# budzik.net
KiCad netlist of a schematic drawn in EAGLE
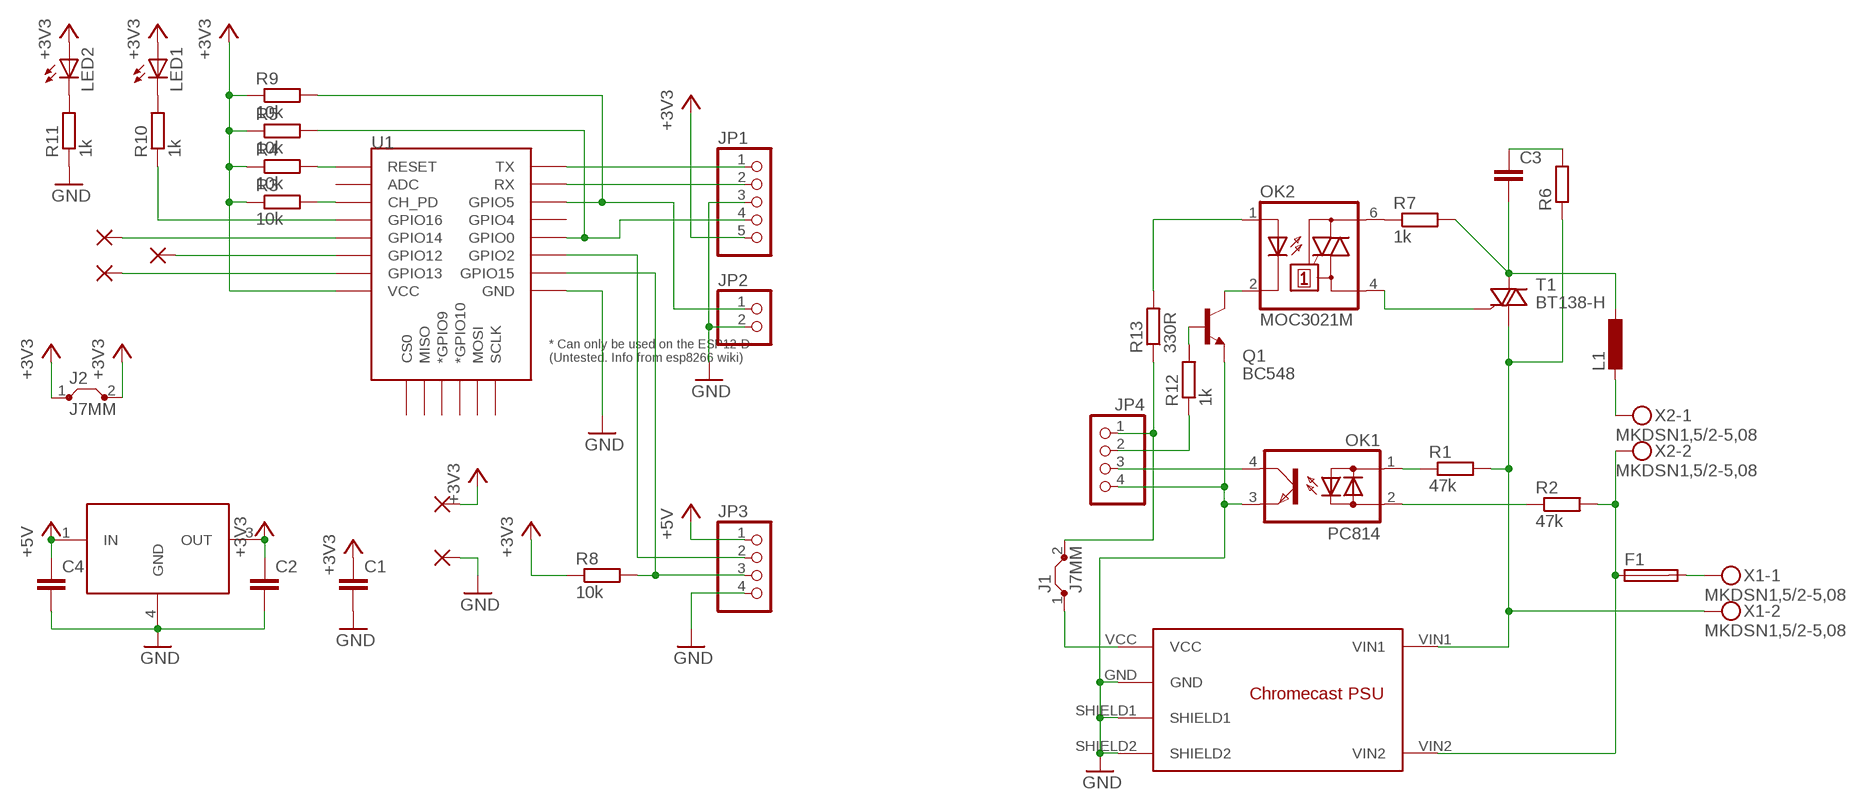
[diagram p0: schematic, sheet 1]

(export (version "E")
  (design (tool "Eeschema 10.0.6"))
  (components
    (comp (ref "C1")
      (value "C-EUC1206")
      (footprint "eagle-import:C1206")
      (libsource (lib "eagle-import") (part "C-EUC1206"))
    )
    (comp (ref "C2")
      (value "C-EUC1206K")
      (footprint "eagle-import:C1206K")
      (libsource (lib "eagle-import") (part "C-EUC1206K"))
    )
    (comp (ref "C3")
      (value "C-EU075-063X106")
      (footprint "eagle-import:C075-063X106")
      (libsource (lib "eagle-import") (part "resistor_C-EU075-063X106"))
    )
    (comp (ref "C4")
      (value "C-EUC1206K")
      (footprint "eagle-import:C1206K")
      (libsource (lib "eagle-import") (part "C-EUC1206K"))
    )
    (comp (ref "F1")
      (value "TR5")
      (footprint "eagle-import:TR5")
      (libsource (lib "eagle-import") (part "TR5"))
    )
    (comp (ref "J1")
      (value "J7MM")
      (footprint "eagle-import:07")
      (libsource (lib "eagle-import") (part "J7MM"))
    )
    (comp (ref "J2")
      (value "J7MM")
      (footprint "eagle-import:07")
      (libsource (lib "eagle-import") (part "J7MM"))
    )
    (comp (ref "JP1")
      (value "PINHD-1X5")
      (footprint "eagle-import:1X05")
      (libsource (lib "eagle-import") (part "PINHD-1X5"))
    )
    (comp (ref "JP2")
      (value "PINHD-1X2")
      (footprint "eagle-import:1X02")
      (libsource (lib "eagle-import") (part "PINHD-1X2"))
    )
    (comp (ref "JP3")
      (value "PINHD-1X4")
      (footprint "eagle-import:1X04")
      (libsource (lib "eagle-import") (part "PINHD-1X4"))
    )
    (comp (ref "JP4")
      (value "PINHD-1X4")
      (footprint "eagle-import:1X04")
      (libsource (lib "eagle-import") (part "PINHD-1X4"))
    )
    (comp (ref "L1")
      (value "L-EU6000-XXX-RC")
      (footprint "eagle-import:6000-XXXX-RC")
      (libsource (lib "eagle-import") (part "L-EU6000-XXX-RC"))
    )
    (comp (ref "LED1")
      (value "LEDSML0805")
      (footprint "eagle-import:SML0805")
      (libsource (lib "eagle-import") (part "LEDSML0805"))
    )
    (comp (ref "LED2")
      (value "LEDSML0805")
      (footprint "eagle-import:SML0805")
      (libsource (lib "eagle-import") (part "LEDSML0805"))
    )
    (comp (ref "OK1")
      (value "PC814")
      (footprint "eagle-import:DIL04")
      (libsource (lib "eagle-import") (part "PC814"))
    )
    (comp (ref "OK2")
      (value "MOC3021M")
      (footprint "eagle-import:DIL06")
      (fields (field (name "MF") "FAIRCHILD SEMICONDUCTOR") (field (name "MPN") "MOC3021-M"))
      (libsource (lib "eagle-import") (part "MOC30M21"))
    )
    (comp (ref "PAD1")
      (value "WIREPAD2,15/1,0")
      (footprint "eagle-import:2,15_1,0")
      (libsource (lib "eagle-import") (part "WIREPAD2,15/1,0"))
    )
    (comp (ref "PAD2")
      (value "WIREPAD2,15/1,0")
      (footprint "eagle-import:2,15_1,0")
      (libsource (lib "eagle-import") (part "WIREPAD2,15/1,0"))
    )
    (comp (ref "PAD3")
      (value "WIREPAD2,15/1,0")
      (footprint "eagle-import:2,15_1,0")
      (libsource (lib "eagle-import") (part "WIREPAD2,15/1,0"))
    )
    (comp (ref "PAD4")
      (value "WIREPAD2,15/1,0")
      (footprint "eagle-import:2,15_1,0")
      (libsource (lib "eagle-import") (part "WIREPAD2,15/1,0"))
    )
    (comp (ref "PAD5")
      (value "WIREPAD2,15/1,0")
      (footprint "eagle-import:2,15_1,0")
      (libsource (lib "eagle-import") (part "WIREPAD2,15/1,0"))
    )
    (comp (ref "Q1")
      (value "BC548")
      (footprint "eagle-import:TO92-EBC")
      (libsource (lib "eagle-import") (part "BC548"))
    )
    (comp (ref "R1")
      (value "47k")
      (footprint "eagle-import:0204_7")
      (libsource (lib "eagle-import") (part "R-EU_0204/7"))
    )
    (comp (ref "R2")
      (value "47k")
      (footprint "eagle-import:0204_7")
      (libsource (lib "eagle-import") (part "R-EU_0204/7"))
    )
    (comp (ref "R3")
      (value "10k")
      (footprint "eagle-import:R0805")
      (libsource (lib "eagle-import") (part "R-EU_R0805"))
    )
    (comp (ref "R4")
      (value "10k")
      (footprint "eagle-import:R0805")
      (libsource (lib "eagle-import") (part "R-EU_R0805"))
    )
    (comp (ref "R5")
      (value "10k")
      (footprint "eagle-import:R0805")
      (libsource (lib "eagle-import") (part "R-EU_R0805"))
    )
    (comp (ref "R6")
      (value "R-EU_0411/3V")
      (footprint "eagle-import:0411V")
      (libsource (lib "eagle-import") (part "resistor_R-EU_0411/3V"))
    )
    (comp (ref "R7")
      (value "1k")
      (footprint "eagle-import:0204_7")
      (libsource (lib "eagle-import") (part "R-EU_0204/7"))
    )
    (comp (ref "R8")
      (value "10k")
      (footprint "eagle-import:R0805")
      (libsource (lib "eagle-import") (part "R-EU_R0805"))
    )
    (comp (ref "R9")
      (value "10k")
      (footprint "eagle-import:R0805")
      (libsource (lib "eagle-import") (part "R-EU_R0805"))
    )
    (comp (ref "R10")
      (value "1k")
      (footprint "eagle-import:R0805")
      (libsource (lib "eagle-import") (part "R-EU_R0805"))
    )
    (comp (ref "R11")
      (value "1k")
      (footprint "eagle-import:R0805")
      (libsource (lib "eagle-import") (part "R-EU_R0805"))
    )
    (comp (ref "R12")
      (value "1k")
      (footprint "eagle-import:R0805")
      (libsource (lib "eagle-import") (part "R-EU_R0805"))
    )
    (comp (ref "R13")
      (value "330R")
      (footprint "eagle-import:R0805")
      (libsource (lib "eagle-import") (part "R-EU_R0805"))
    )
    (comp (ref "T1")
      (value "BT138-H")
      (footprint "eagle-import:TO220BH")
      (libsource (lib "eagle-import") (part "BT138-H"))
    )
    (comp (ref "U$1")
      (value "CHROMECAST-PSU")
      (footprint "eagle-import:CHROMECAST-PSU-UPSIDE-DOWN")
      (libsource (lib "eagle-import") (part "CHROMECAST-PSU"))
    )
    (comp (ref "U$2")
      (value "LF33A")
      (footprint "eagle-import:DPAK")
      (libsource (lib "eagle-import") (part "LF33A"))
    )
    (comp (ref "U1")
      (value "ESP12ESMD")
      (footprint "eagle-import:ESP12E-SMD")
      (libsource (lib "eagle-import") (part "ESP12ESMD"))
    )
    (comp (ref "X1")
      (value "MKDSN1,5/2-5,08")
      (footprint "eagle-import:MKDSN1,5_2-5,08")
      (libsource (lib "eagle-import") (part "MKDSN1,5/2-5,08"))
    )
    (comp (ref "X2")
      (value "MKDSN1,5/2-5,08")
      (footprint "eagle-import:MKDSN1,5_2-5,08")
      (libsource (lib "eagle-import") (part "MKDSN1,5/2-5,08"))
    )
  )
  (nets
    (net (code "1") (name "+3V3") (class "Default")
      (node (ref "C1") (pin "1") (pinfunction "1_1") (pintype "passive"))
      (node (ref "C2") (pin "1") (pinfunction "1_1") (pintype "passive"))
      (node (ref "J2") (pin "1") (pinfunction "1_1") (pintype "passive"))
      (node (ref "J2") (pin "2") (pinfunction "2_2") (pintype "passive"))
      (node (ref "JP1") (pin "5") (pinfunction "5_5") (pintype "passive"))
      (node (ref "LED1") (pin "A") (pinfunction "A_A") (pintype "passive"))
      (node (ref "LED2") (pin "A") (pinfunction "A_A") (pintype "passive"))
      (node (ref "PAD4") (pin "1") (pinfunction "P_1") (pintype "passive"))
      (node (ref "R3") (pin "1") (pinfunction "1_1") (pintype "passive"))
      (node (ref "R4") (pin "1") (pinfunction "1_1") (pintype "passive"))
      (node (ref "R5") (pin "1") (pinfunction "1_1") (pintype "passive"))
      (node (ref "R8") (pin "1") (pinfunction "1_1") (pintype "passive"))
      (node (ref "R9") (pin "1") (pinfunction "1_1") (pintype "passive"))
      (node (ref "U$2") (pin "3") (pinfunction "OUT_3") (pintype "bidirectional"))
      (node (ref "U1") (pin "VCC") (pinfunction "VCC_VCC") (pintype "bidirectional"))
    )
    (net (code "2") (name "+5V") (class "Default")
      (node (ref "C4") (pin "1") (pinfunction "1_1") (pintype "passive"))
      (node (ref "JP3") (pin "1") (pinfunction "1_1") (pintype "passive"))
      (node (ref "U$2") (pin "1") (pinfunction "IN_1") (pintype "bidirectional"))
    )
    (net (code "3") (name "GND") (class "Default")
      (node (ref "C1") (pin "2") (pinfunction "2_2") (pintype "passive"))
      (node (ref "C2") (pin "2") (pinfunction "2_2") (pintype "passive"))
      (node (ref "C4") (pin "2") (pinfunction "2_2") (pintype "passive"))
      (node (ref "JP1") (pin "3") (pinfunction "3_3") (pintype "passive"))
      (node (ref "JP2") (pin "2") (pinfunction "2_2") (pintype "passive"))
      (node (ref "JP3") (pin "4") (pinfunction "4_4") (pintype "passive"))
      (node (ref "JP4") (pin "4") (pinfunction "4_4") (pintype "passive"))
      (node (ref "OK1") (pin "3") (pinfunction "E_3") (pintype "passive"))
      (node (ref "PAD5") (pin "1") (pinfunction "P_1") (pintype "passive"))
      (node (ref "Q1") (pin "E") (pinfunction "E_E") (pintype "passive"))
      (node (ref "R11") (pin "1") (pinfunction "1_1") (pintype "passive"))
      (node (ref "U$1") (pin "GND") (pinfunction "GND_GND") (pintype "bidirectional"))
      (node (ref "U$1") (pin "SHIELD1") (pinfunction "SHIELD1_SHIELD1") (pintype "bidirectional"))
      (node (ref "U$1") (pin "SHIELD2") (pinfunction "SHIELD2_SHIELD2") (pintype "bidirectional"))
      (node (ref "U$2") (pin "4") (pinfunction "GND_4") (pintype "bidirectional"))
      (node (ref "U1") (pin "GND") (pinfunction "GND_GND") (pintype "bidirectional"))
    )
    (net (code "4") (name "Net-(C3-Pad1)") (class "Default")
      (node (ref "C3") (pin "1") (pinfunction "1_1") (pintype "passive"))
      (node (ref "R6") (pin "2") (pinfunction "2_2") (pintype "passive"))
    )
    (net (code "5") (name "Net-(J1-Pad1)") (class "Default")
      (node (ref "J1") (pin "1") (pinfunction "1_1") (pintype "passive"))
      (node (ref "U$1") (pin "VCC") (pinfunction "VCC_VCC") (pintype "bidirectional"))
    )
    (net (code "6") (name "Net-(J1-Pad2)") (class "Default")
      (node (ref "J1") (pin "2") (pinfunction "2_2") (pintype "passive"))
      (node (ref "JP4") (pin "1") (pinfunction "1_1") (pintype "passive"))
      (node (ref "R13") (pin "1") (pinfunction "1_1") (pintype "passive"))
    )
    (net (code "7") (name "Net-(JP1-Pad4)") (class "Default")
      (node (ref "JP1") (pin "4") (pinfunction "4_4") (pintype "passive"))
      (node (ref "R5") (pin "2") (pinfunction "2_2") (pintype "passive"))
      (node (ref "U1") (pin "GPIO0") (pinfunction "GPIO0_GPIO0") (pintype "bidirectional"))
    )
    (net (code "8") (name "Net-(JP2-Pad1)") (class "Default")
      (node (ref "JP2") (pin "1") (pinfunction "1_1") (pintype "passive"))
      (node (ref "R9") (pin "2") (pinfunction "2_2") (pintype "passive"))
      (node (ref "U1") (pin "GPIO5") (pinfunction "GPIO5_GPIO5") (pintype "bidirectional"))
    )
    (net (code "9") (name "Net-(JP3-Pad2)") (class "Default")
      (node (ref "JP3") (pin "2") (pinfunction "2_2") (pintype "passive"))
      (node (ref "U1") (pin "GPIO2") (pinfunction "GPIO2_GPIO2") (pintype "bidirectional"))
    )
    (net (code "10") (name "Net-(JP3-Pad3)") (class "Default")
      (node (ref "JP3") (pin "3") (pinfunction "3_3") (pintype "passive"))
      (node (ref "R8") (pin "2") (pinfunction "2_2") (pintype "passive"))
      (node (ref "U1") (pin "GPIO15") (pinfunction "GPIO15_GPIO15") (pintype "bidirectional"))
    )
    (net (code "11") (name "Net-(JP4-Pad2)") (class "Default")
      (node (ref "JP4") (pin "2") (pinfunction "2_2") (pintype "passive"))
      (node (ref "R12") (pin "1") (pinfunction "1_1") (pintype "passive"))
    )
    (net (code "12") (name "Net-(LED1-PadC)") (class "Default")
      (node (ref "LED1") (pin "C") (pinfunction "C_C") (pintype "passive"))
      (node (ref "R10") (pin "2") (pinfunction "2_2") (pintype "passive"))
    )
    (net (code "13") (name "Net-(LED2-PadC)") (class "Default")
      (node (ref "LED2") (pin "C") (pinfunction "C_C") (pintype "passive"))
      (node (ref "R11") (pin "2") (pinfunction "2_2") (pintype "passive"))
    )
    (net (code "14") (name "Net-(OK1-AC1)") (class "Default")
      (node (ref "OK1") (pin "1") (pinfunction "AC1_1") (pintype "passive"))
      (node (ref "R1") (pin "1") (pinfunction "1_1") (pintype "passive"))
    )
    (net (code "15") (name "Net-(OK1-AC2)") (class "Default")
      (node (ref "OK1") (pin "2") (pinfunction "AC2_2") (pintype "passive"))
      (node (ref "R2") (pin "1") (pinfunction "1_1") (pintype "passive"))
    )
    (net (code "16") (name "Net-(OK1-C)") (class "Default")
      (node (ref "JP4") (pin "3") (pinfunction "3_3") (pintype "passive"))
      (node (ref "OK1") (pin "4") (pinfunction "C_4") (pintype "passive"))
    )
    (net (code "17") (name "Net-(OK2-A)") (class "Default")
      (node (ref "OK2") (pin "1") (pinfunction "A_1") (pintype "passive"))
      (node (ref "R13") (pin "2") (pinfunction "2_2") (pintype "passive"))
    )
    (net (code "18") (name "Net-(OK2-A1)") (class "Default")
      (node (ref "OK2") (pin "4") (pinfunction "A1_4") (pintype "passive"))
      (node (ref "T1") (pin "G") (pinfunction "G_G") (pintype "passive"))
    )
    (net (code "19") (name "Net-(OK2-A2)") (class "Default")
      (node (ref "OK2") (pin "6") (pinfunction "A2_6") (pintype "passive"))
      (node (ref "R7") (pin "1") (pinfunction "1_1") (pintype "passive"))
    )
    (net (code "20") (name "Net-(OK2-C)") (class "Default")
      (node (ref "OK2") (pin "2") (pinfunction "C_2") (pintype "passive"))
      (node (ref "Q1") (pin "C") (pinfunction "C_C") (pintype "passive"))
    )
    (net (code "21") (name "Net-(PAD1-P)") (class "Default")
      (node (ref "PAD1") (pin "1") (pinfunction "P_1") (pintype "passive"))
      (node (ref "U1") (pin "GPIO13") (pinfunction "GPIO13_GPIO13") (pintype "bidirectional"))
    )
    (net (code "22") (name "Net-(PAD2-P)") (class "Default")
      (node (ref "PAD2") (pin "1") (pinfunction "P_1") (pintype "passive"))
      (node (ref "U1") (pin "GPIO14") (pinfunction "GPIO14_GPIO14") (pintype "bidirectional"))
    )
    (net (code "23") (name "Net-(PAD3-P)") (class "Default")
      (node (ref "PAD3") (pin "1") (pinfunction "P_1") (pintype "passive"))
      (node (ref "U1") (pin "GPIO12") (pinfunction "GPIO12_GPIO12") (pintype "bidirectional"))
    )
    (net (code "24") (name "Net-(Q1-PadB)") (class "Default")
      (node (ref "Q1") (pin "B") (pinfunction "B_B") (pintype "passive"))
      (node (ref "R12") (pin "2") (pinfunction "2_2") (pintype "passive"))
    )
    (net (code "25") (name "Net-(R3-Pad2)") (class "Default")
      (node (ref "R3") (pin "2") (pinfunction "2_2") (pintype "passive"))
      (node (ref "U1") (pin "CH_PD") (pinfunction "CH_PD_CH_PD") (pintype "bidirectional"))
    )
    (net (code "26") (name "Net-(R4-Pad2)") (class "Default")
      (node (ref "R4") (pin "2") (pinfunction "2_2") (pintype "passive"))
      (node (ref "U1") (pin "RESET") (pinfunction "RESET_RESET") (pintype "bidirectional"))
    )
    (net (code "27") (name "Net-(R10-Pad1)") (class "Default")
      (node (ref "R10") (pin "1") (pinfunction "1_1") (pintype "passive"))
      (node (ref "U1") (pin "GPIO16") (pinfunction "GPIO16_GPIO16") (pintype "bidirectional"))
    )
    (net (code "28") (name "Net-(T1-A1)") (class "Default")
      (node (ref "R1") (pin "2") (pinfunction "2_2") (pintype "passive"))
      (node (ref "R6") (pin "1") (pinfunction "1_1") (pintype "passive"))
      (node (ref "T1") (pin "T1") (pinfunction "A1_T1") (pintype "passive"))
      (node (ref "U$1") (pin "VIN1") (pinfunction "VIN1_VIN1") (pintype "bidirectional"))
      (node (ref "X1") (pin "2") (pinfunction "KL_2") (pintype "passive"))
    )
    (net (code "29") (name "Net-(T1-A2)") (class "Default")
      (node (ref "C3") (pin "2") (pinfunction "2_2") (pintype "passive"))
      (node (ref "L1") (pin "1") (pinfunction "1_1") (pintype "passive"))
      (node (ref "R7") (pin "2") (pinfunction "2_2") (pintype "passive"))
      (node (ref "T1") (pin "T2") (pinfunction "A2_T2") (pintype "passive"))
    )
    (net (code "30") (name "Net-(U1-RX)") (class "Default")
      (node (ref "JP1") (pin "2") (pinfunction "2_2") (pintype "passive"))
      (node (ref "U1") (pin "RXD0") (pinfunction "RX_RXD0") (pintype "bidirectional"))
    )
    (net (code "31") (name "Net-(U1-TX)") (class "Default")
      (node (ref "JP1") (pin "1") (pinfunction "1_1") (pintype "passive"))
      (node (ref "U1") (pin "TXD0") (pinfunction "TX_TXD0") (pintype "bidirectional"))
    )
    (net (code "32") (name "Net-(X1A-KL)") (class "Default")
      (node (ref "F1") (pin "2") (pinfunction "2_2") (pintype "passive"))
      (node (ref "X1") (pin "1") (pinfunction "KL_1") (pintype "passive"))
    )
    (net (code "33") (name "Net-(X2A-KL)") (class "Default")
      (node (ref "L1") (pin "2") (pinfunction "2_2") (pintype "passive"))
      (node (ref "X2") (pin "1") (pinfunction "KL_1") (pintype "passive"))
    )
    (net (code "34") (name "Net-(X2B-KL)") (class "Default")
      (node (ref "F1") (pin "1") (pinfunction "1_1") (pintype "passive"))
      (node (ref "R2") (pin "2") (pinfunction "2_2") (pintype "passive"))
      (node (ref "U$1") (pin "VIN2") (pinfunction "VIN2_VIN2") (pintype "bidirectional"))
      (node (ref "X2") (pin "2") (pinfunction "KL_2") (pintype "passive"))
    )
    (net (code "35") (name "unconnected-(U1-*GPIO9-PadGPIO9)") (class "Default")
      (node (ref "U1") (pin "GPIO9") (pinfunction "*GPIO9_GPIO9") (pintype "bidirectional"))
    )
    (net (code "36") (name "unconnected-(U1-*GPIO10-PadGPIO10)") (class "Default")
      (node (ref "U1") (pin "GPIO10") (pinfunction "*GPIO10_GPIO10") (pintype "bidirectional"))
    )
    (net (code "37") (name "unconnected-(U1-PadADC)") (class "Default")
      (node (ref "U1") (pin "ADC") (pinfunction "ADC_ADC") (pintype "bidirectional"))
    )
    (net (code "38") (name "unconnected-(U1-PadCS0)") (class "Default")
      (node (ref "U1") (pin "CS0") (pinfunction "CS0_CS0") (pintype "bidirectional"))
    )
    (net (code "39") (name "unconnected-(U1-PadGPIO4)") (class "Default")
      (node (ref "U1") (pin "GPIO4") (pinfunction "GPIO4_GPIO4") (pintype "bidirectional"))
    )
    (net (code "40") (name "unconnected-(U1-PadMISO)") (class "Default")
      (node (ref "U1") (pin "MISO") (pinfunction "MISO_MISO") (pintype "bidirectional"))
    )
    (net (code "41") (name "unconnected-(U1-PadMOSI)") (class "Default")
      (node (ref "U1") (pin "MOSI") (pinfunction "MOSI_MOSI") (pintype "bidirectional"))
    )
    (net (code "42") (name "unconnected-(U1-PadSCLK)") (class "Default")
      (node (ref "U1") (pin "SCLK") (pinfunction "SCLK_SCLK") (pintype "bidirectional"))
    )
  )
)
